# car-dashboard_v1.net
KiCad netlist of a schematic drawn in EAGLE
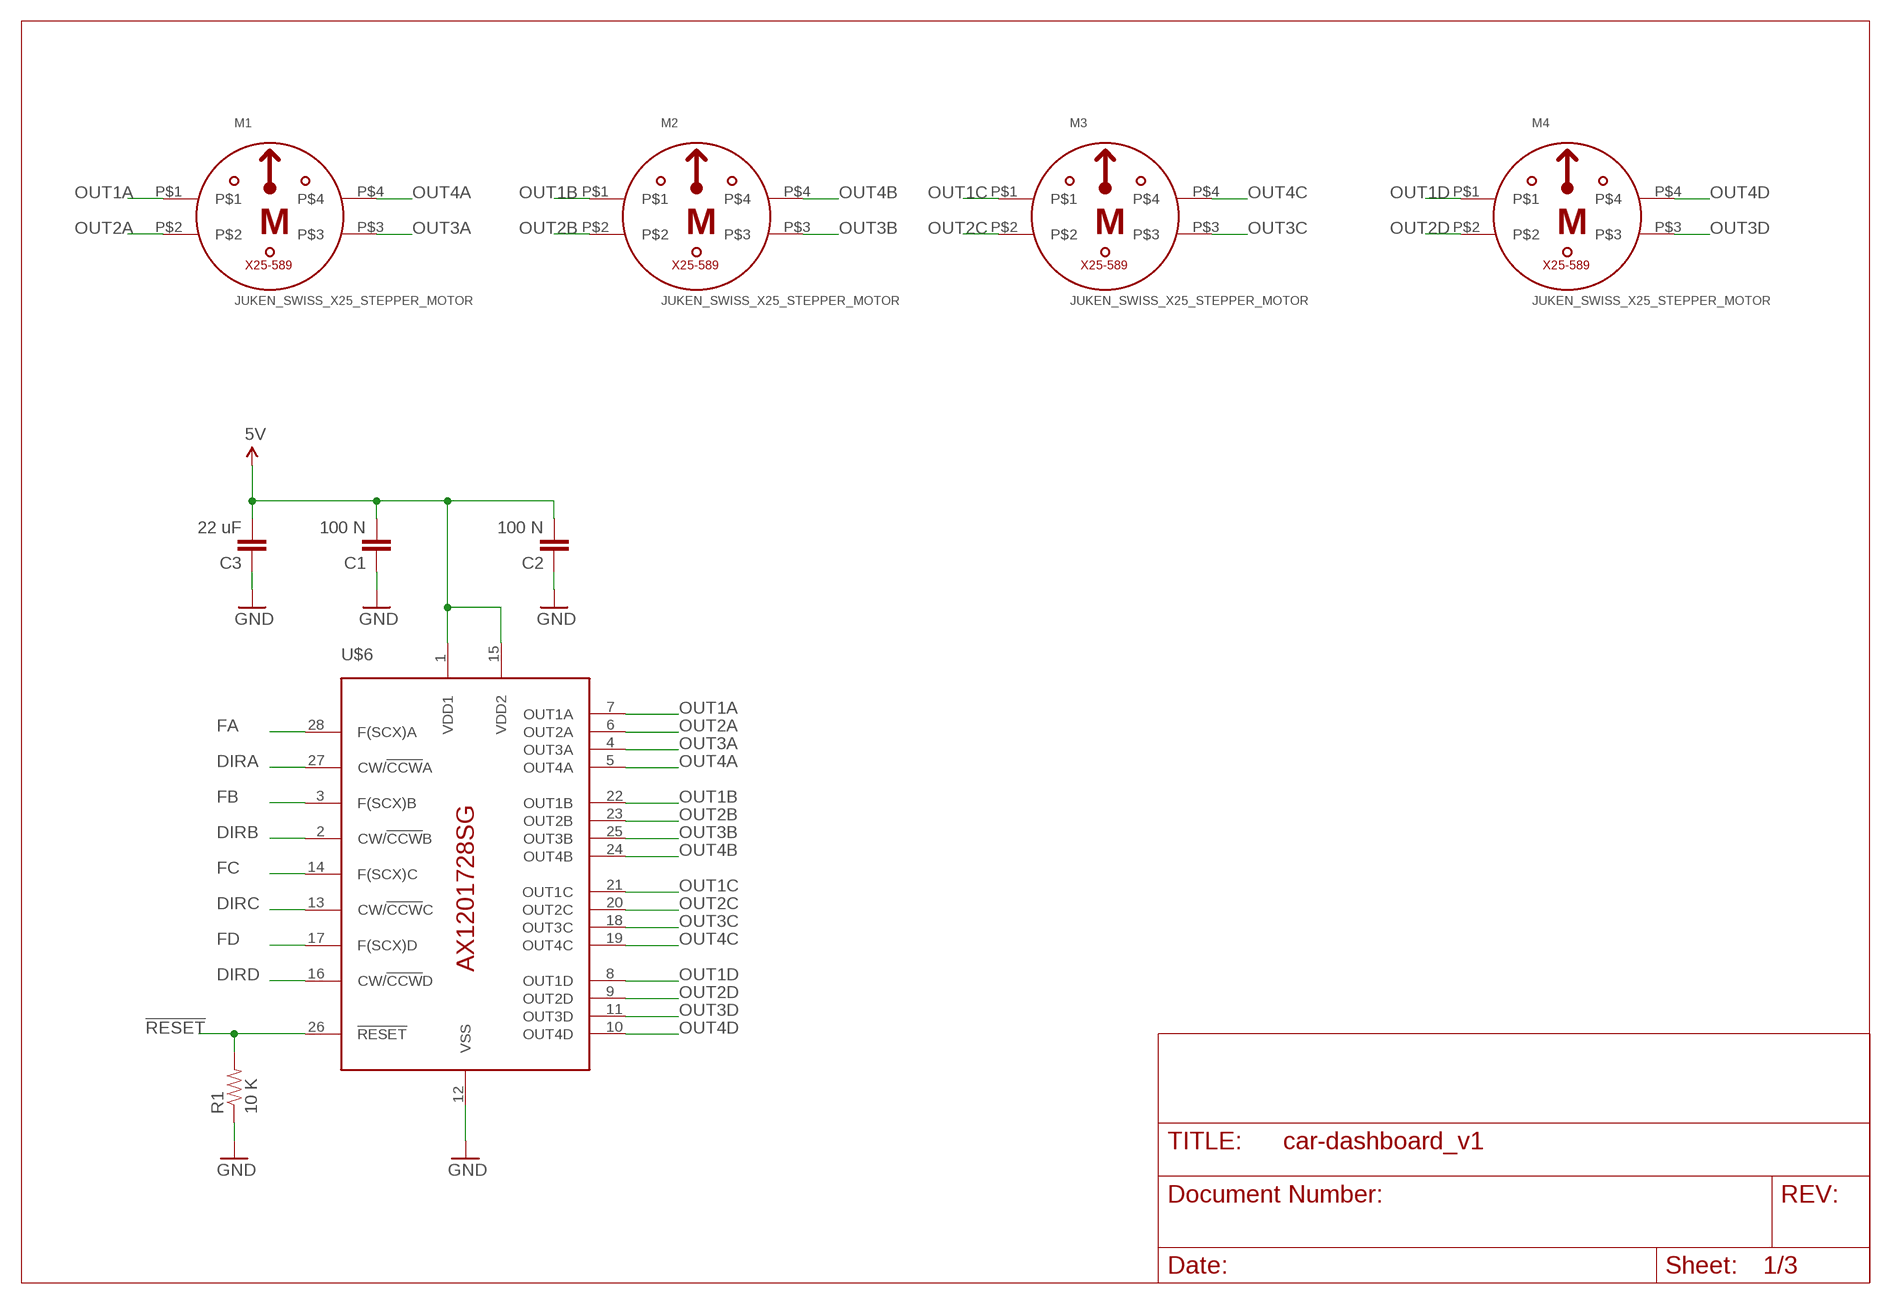
[diagram p0: schematic, sheet 1]
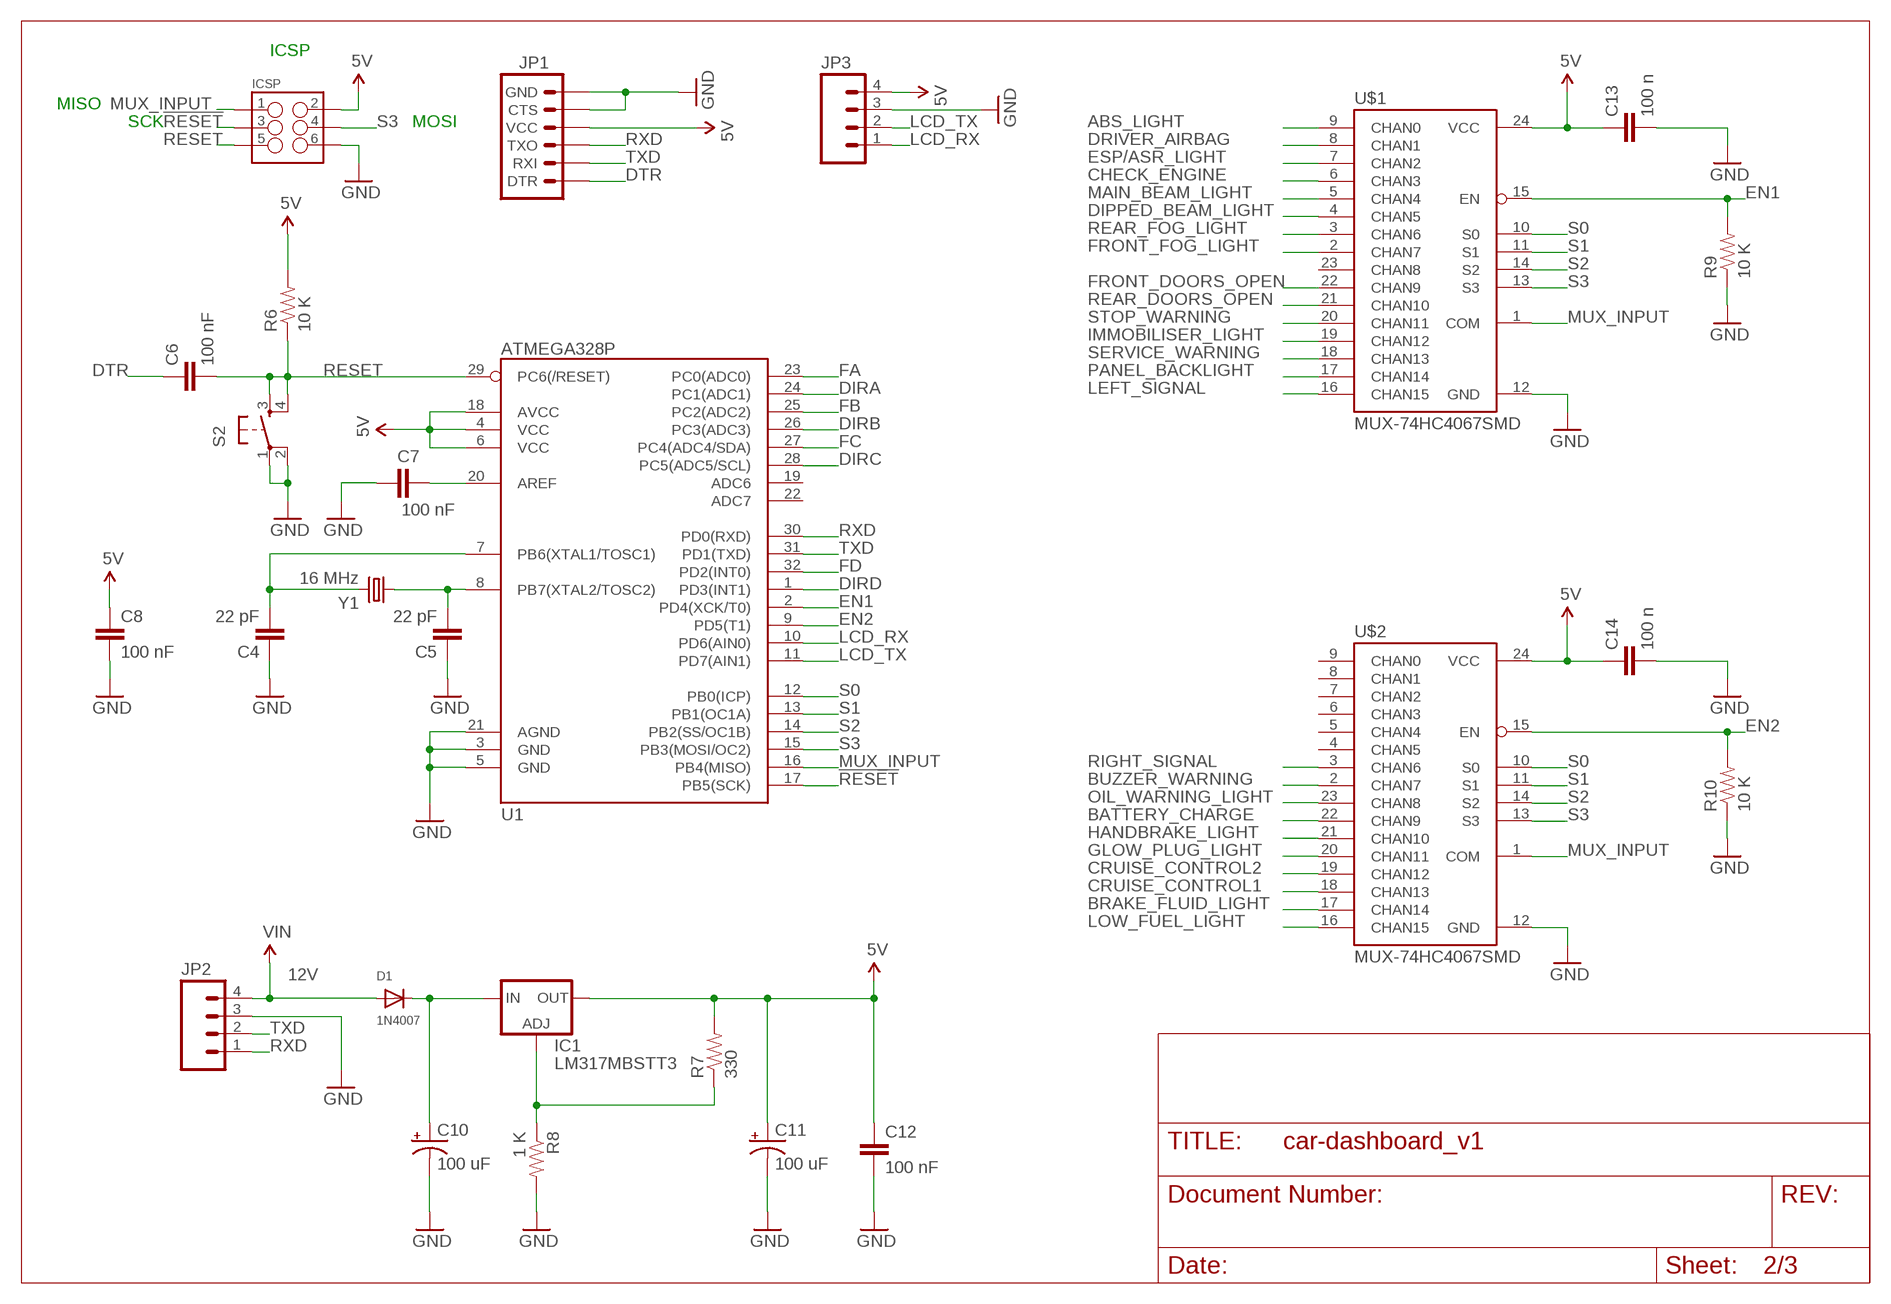
[diagram p1: schematic, sheet 2]
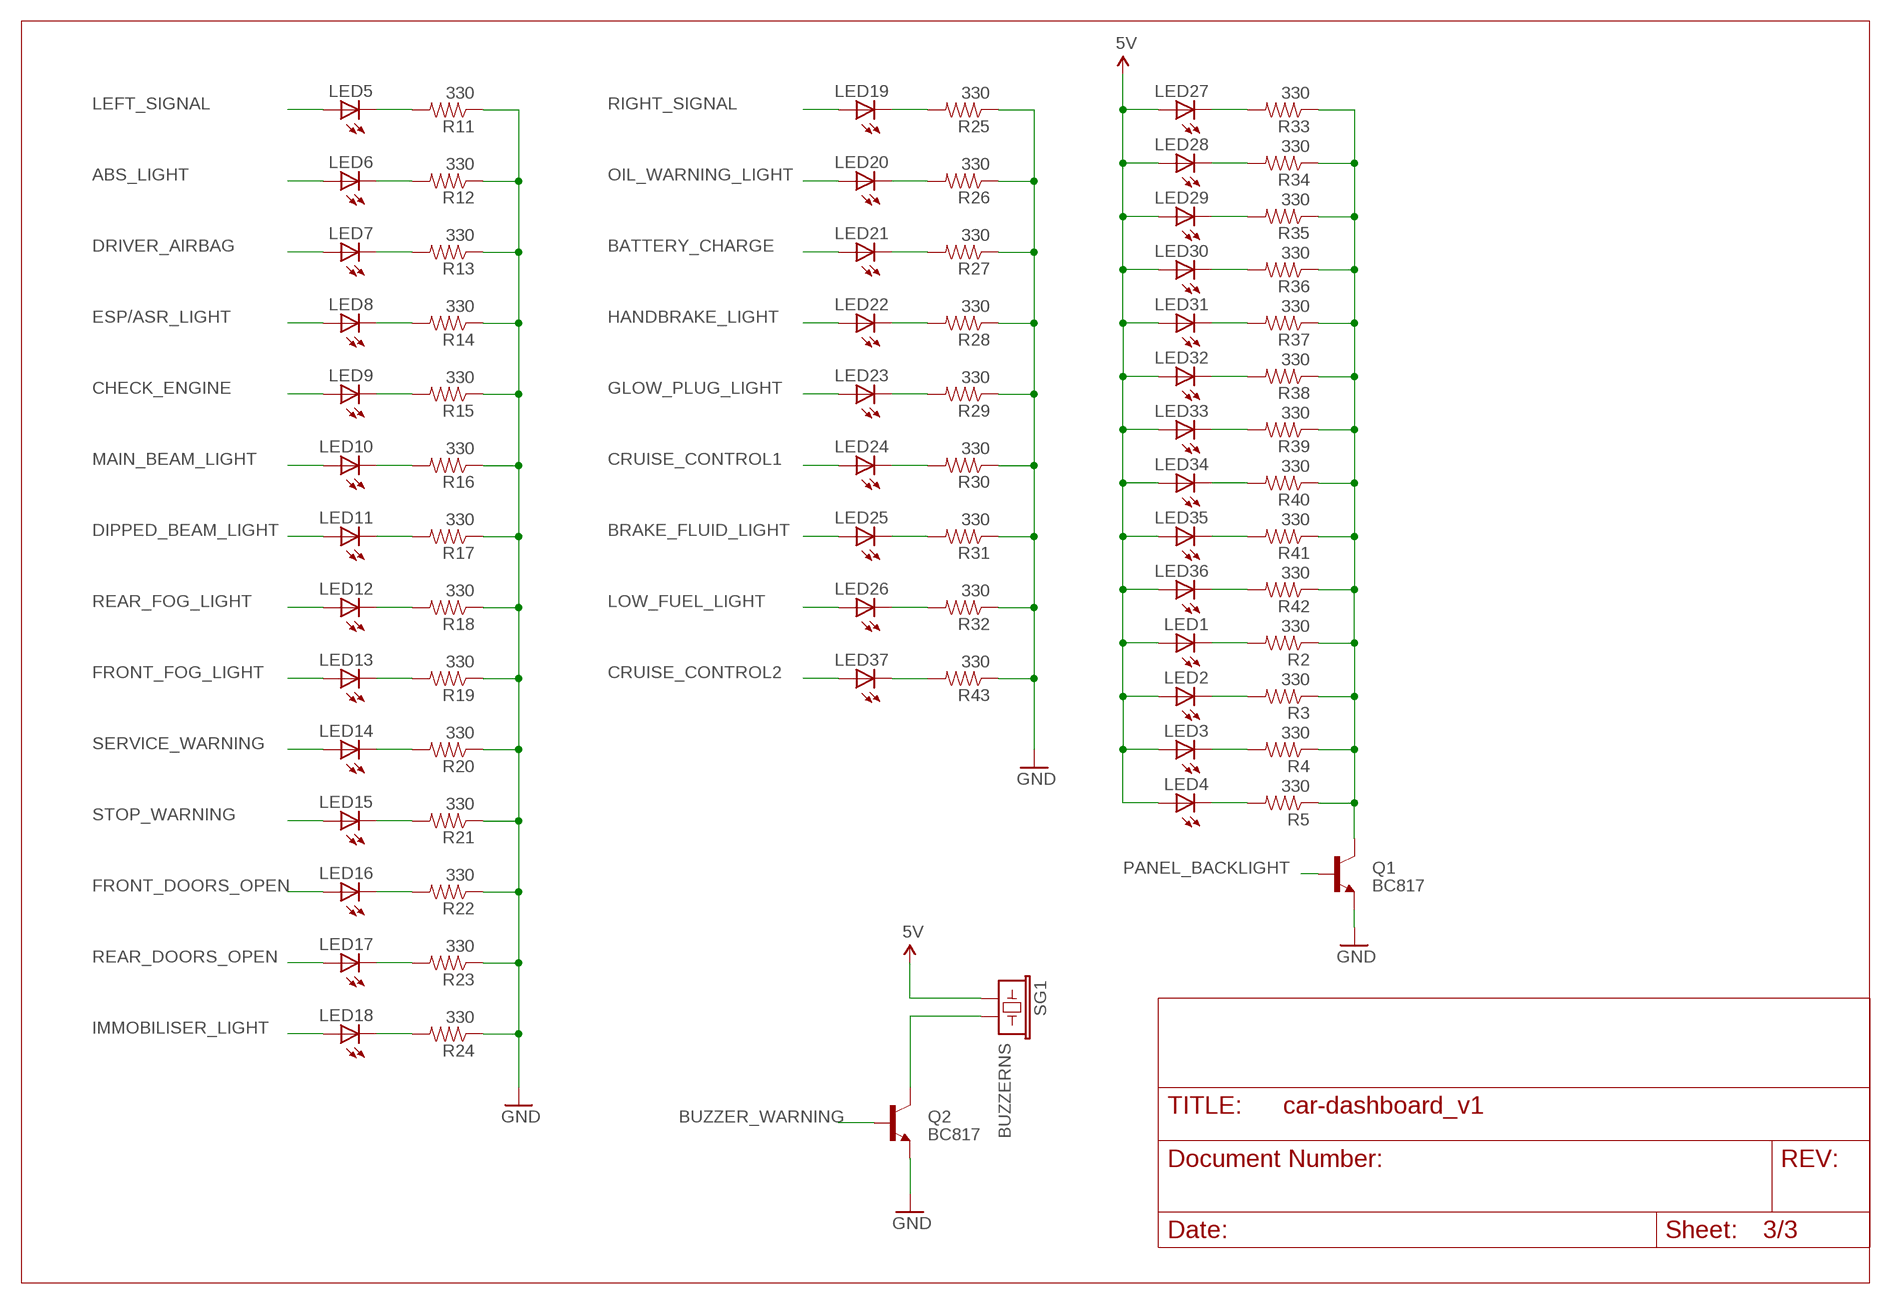
[diagram p2: schematic, sheet 3]

(export (version "E")
  (design (tool "Eeschema 10.0.6"))
  (components
    (comp (ref "C4")
      (value "22 pF")
      (footprint "eagle-import:C0805")
      (libsource (lib "eagle-import") (part "CAPC0805"))
    )
    (comp (ref "C5")
      (value "22 pF")
      (footprint "eagle-import:C0805")
      (libsource (lib "eagle-import") (part "CAPC0805"))
    )
    (comp (ref "C6")
      (value "100 nF")
      (footprint "eagle-import:C0805")
      (libsource (lib "eagle-import") (part "CAPC0805"))
    )
    (comp (ref "C7")
      (value "100 nF")
      (footprint "eagle-import:C0805")
      (libsource (lib "eagle-import") (part "CAPC0805"))
    )
    (comp (ref "C8")
      (value "100 nF")
      (footprint "eagle-import:C0805")
      (libsource (lib "eagle-import") (part "CAPC0805"))
    )
    (comp (ref "C10")
      (value "100 uF")
      (footprint "eagle-import:PANASONIC_F")
      (libsource (lib "eagle-import") (part "CPOL-USF"))
    )
    (comp (ref "C11")
      (value "100 uF")
      (footprint "eagle-import:PANASONIC_F")
      (libsource (lib "eagle-import") (part "CPOL-USF"))
    )
    (comp (ref "C12")
      (value "100 nF")
      (footprint "eagle-import:C0805")
      (libsource (lib "eagle-import") (part "CAPC0805"))
    )
    (comp (ref "C13")
      (value "100 n")
      (footprint "eagle-import:C0805")
      (libsource (lib "eagle-import") (part "CAP0805"))
    )
    (comp (ref "C14")
      (value "100 n")
      (footprint "eagle-import:C0805")
      (libsource (lib "eagle-import") (part "CAP0805"))
    )
    (comp (ref "D1")
      (value "1N4007")
      (footprint "eagle-import:SMADIODE")
      (libsource (lib "eagle-import") (part "DIODESMA"))
    )
    (comp (ref "IC1")
      (value "LM317MBSTT3")
      (footprint "eagle-import:SOT223")
      (libsource (lib "eagle-import") (part "LM317?MBSTT3"))
    )
    (comp (ref "ICSP")
      (value "M03X22X3_SILK_SM")
      (footprint "eagle-import:2X3")
      (libsource (lib "eagle-import") (part "M03X22X3_SILK_SM"))
    )
    (comp (ref "JP1")
      (value "ARDUINO_SERIAL_PROGRAMPTH")
      (footprint "eagle-import:1X06")
      (libsource (lib "eagle-import") (part "ARDUINO_SERIAL_PROGRAMPTH"))
    )
    (comp (ref "JP2")
      (value "M04POLAR")
      (footprint "eagle-import:MOLEX-1X4")
      (libsource (lib "eagle-import") (part "M04POLAR"))
    )
    (comp (ref "JP3")
      (value "M04POLAR")
      (footprint "eagle-import:MOLEX-1X4")
      (libsource (lib "eagle-import") (part "M04POLAR"))
    )
    (comp (ref "R6")
      (value "10 K")
      (footprint "eagle-import:R0805")
      (libsource (lib "eagle-import") (part "RESISTOR0805-RES"))
    )
    (comp (ref "R7")
      (value "330")
      (footprint "eagle-import:R0805")
      (libsource (lib "eagle-import") (part "RESISTOR0805-RES"))
    )
    (comp (ref "R8")
      (value "1 K")
      (footprint "eagle-import:R0805")
      (libsource (lib "eagle-import") (part "RESISTOR0805-RES"))
    )
    (comp (ref "R9")
      (value "10 K")
      (footprint "eagle-import:R0805")
      (libsource (lib "eagle-import") (part "RESISTOR0805-RES"))
    )
    (comp (ref "R10")
      (value "10 K")
      (footprint "eagle-import:R0805")
      (libsource (lib "eagle-import") (part "RESISTOR0805-RES"))
    )
    (comp (ref "S2")
      (value "TAC_SWITCHPTH")
      (footprint "eagle-import:TACTILE-PTH")
      (libsource (lib "eagle-import") (part "TAC_SWITCHPTH"))
    )
    (comp (ref "U$1")
      (value "MUX-74HC4067SMD")
      (footprint "eagle-import:SSOP24")
      (libsource (lib "eagle-import") (part "MUX-74HC4067SMD"))
    )
    (comp (ref "U$2")
      (value "MUX-74HC4067SMD")
      (footprint "eagle-import:SSOP24")
      (libsource (lib "eagle-import") (part "MUX-74HC4067SMD"))
    )
    (comp (ref "U1")
      (value "ATMEGA328P")
      (footprint "eagle-import:TQFP32-08")
      (libsource (lib "eagle-import") (part "ATMEGA328_SMT"))
    )
    (comp (ref "Y1")
      (value "16 MHz")
      (footprint "eagle-import:HC49UP")
      (libsource (lib "eagle-import") (part "CRYSTALSMD"))
    )
    (comp (ref "LED1")
      (value "LEDCHIPLED_0805")
      (footprint "eagle-import:CHIPLED_0805")
      (libsource (lib "eagle-import") (part "LEDCHIPLED_0805"))
    )
    (comp (ref "LED2")
      (value "LEDCHIPLED_0805")
      (footprint "eagle-import:CHIPLED_0805")
      (libsource (lib "eagle-import") (part "LEDCHIPLED_0805"))
    )
    (comp (ref "LED3")
      (value "LEDCHIPLED_0805")
      (footprint "eagle-import:CHIPLED_0805")
      (libsource (lib "eagle-import") (part "LEDCHIPLED_0805"))
    )
    (comp (ref "LED4")
      (value "LEDCHIPLED_0805")
      (footprint "eagle-import:CHIPLED_0805")
      (libsource (lib "eagle-import") (part "LEDCHIPLED_0805"))
    )
    (comp (ref "LED5")
      (value "LEDCHIPLED_0805")
      (footprint "eagle-import:CHIPLED_0805")
      (libsource (lib "eagle-import") (part "LEDCHIPLED_0805"))
    )
    (comp (ref "LED6")
      (value "LEDCHIPLED_0805")
      (footprint "eagle-import:CHIPLED_0805")
      (libsource (lib "eagle-import") (part "LEDCHIPLED_0805"))
    )
    (comp (ref "LED7")
      (value "LEDCHIPLED_0805")
      (footprint "eagle-import:CHIPLED_0805")
      (libsource (lib "eagle-import") (part "LEDCHIPLED_0805"))
    )
    (comp (ref "LED8")
      (value "LEDCHIPLED_0805")
      (footprint "eagle-import:CHIPLED_0805")
      (libsource (lib "eagle-import") (part "LEDCHIPLED_0805"))
    )
    (comp (ref "LED9")
      (value "LEDCHIPLED_0805")
      (footprint "eagle-import:CHIPLED_0805")
      (libsource (lib "eagle-import") (part "LEDCHIPLED_0805"))
    )
    (comp (ref "LED10")
      (value "LEDCHIPLED_0805")
      (footprint "eagle-import:CHIPLED_0805")
      (libsource (lib "eagle-import") (part "LEDCHIPLED_0805"))
    )
    (comp (ref "LED11")
      (value "LEDCHIPLED_0805")
      (footprint "eagle-import:CHIPLED_0805")
      (libsource (lib "eagle-import") (part "LEDCHIPLED_0805"))
    )
    (comp (ref "LED12")
      (value "LEDCHIPLED_0805")
      (footprint "eagle-import:CHIPLED_0805")
      (libsource (lib "eagle-import") (part "LEDCHIPLED_0805"))
    )
    (comp (ref "LED13")
      (value "LEDCHIPLED_0805")
      (footprint "eagle-import:CHIPLED_0805")
      (libsource (lib "eagle-import") (part "LEDCHIPLED_0805"))
    )
    (comp (ref "LED14")
      (value "LEDCHIPLED_0805")
      (footprint "eagle-import:CHIPLED_0805")
      (libsource (lib "eagle-import") (part "LEDCHIPLED_0805"))
    )
    (comp (ref "LED15")
      (value "LEDCHIPLED_0805")
      (footprint "eagle-import:CHIPLED_0805")
      (libsource (lib "eagle-import") (part "LEDCHIPLED_0805"))
    )
    (comp (ref "LED16")
      (value "LEDCHIPLED_0805")
      (footprint "eagle-import:CHIPLED_0805")
      (libsource (lib "eagle-import") (part "LEDCHIPLED_0805"))
    )
    (comp (ref "LED17")
      (value "LEDCHIPLED_0805")
      (footprint "eagle-import:CHIPLED_0805")
      (libsource (lib "eagle-import") (part "LEDCHIPLED_0805"))
    )
    (comp (ref "LED18")
      (value "LEDCHIPLED_0805")
      (footprint "eagle-import:CHIPLED_0805")
      (libsource (lib "eagle-import") (part "LEDCHIPLED_0805"))
    )
    (comp (ref "LED19")
      (value "LEDCHIPLED_0805")
      (footprint "eagle-import:CHIPLED_0805")
      (libsource (lib "eagle-import") (part "LEDCHIPLED_0805"))
    )
    (comp (ref "LED20")
      (value "LEDCHIPLED_0805")
      (footprint "eagle-import:CHIPLED_0805")
      (libsource (lib "eagle-import") (part "LEDCHIPLED_0805"))
    )
    (comp (ref "LED21")
      (value "LEDCHIPLED_0805")
      (footprint "eagle-import:CHIPLED_0805")
      (libsource (lib "eagle-import") (part "LEDCHIPLED_0805"))
    )
    (comp (ref "LED22")
      (value "LEDCHIPLED_0805")
      (footprint "eagle-import:CHIPLED_0805")
      (libsource (lib "eagle-import") (part "LEDCHIPLED_0805"))
    )
    (comp (ref "LED23")
      (value "LEDCHIPLED_0805")
      (footprint "eagle-import:CHIPLED_0805")
      (libsource (lib "eagle-import") (part "LEDCHIPLED_0805"))
    )
    (comp (ref "LED24")
      (value "LEDCHIPLED_0805")
      (footprint "eagle-import:CHIPLED_0805")
      (libsource (lib "eagle-import") (part "LEDCHIPLED_0805"))
    )
    (comp (ref "LED25")
      (value "LEDCHIPLED_0805")
      (footprint "eagle-import:CHIPLED_0805")
      (libsource (lib "eagle-import") (part "LEDCHIPLED_0805"))
    )
    (comp (ref "LED26")
      (value "LEDCHIPLED_0805")
      (footprint "eagle-import:CHIPLED_0805")
      (libsource (lib "eagle-import") (part "LEDCHIPLED_0805"))
    )
    (comp (ref "LED27")
      (value "LEDCHIPLED_0805")
      (footprint "eagle-import:CHIPLED_0805")
      (libsource (lib "eagle-import") (part "LEDCHIPLED_0805"))
    )
    (comp (ref "LED28")
      (value "LEDCHIPLED_0805")
      (footprint "eagle-import:CHIPLED_0805")
      (libsource (lib "eagle-import") (part "LEDCHIPLED_0805"))
    )
    (comp (ref "LED29")
      (value "LEDCHIPLED_0805")
      (footprint "eagle-import:CHIPLED_0805")
      (libsource (lib "eagle-import") (part "LEDCHIPLED_0805"))
    )
    (comp (ref "LED30")
      (value "LEDCHIPLED_0805")
      (footprint "eagle-import:CHIPLED_0805")
      (libsource (lib "eagle-import") (part "LEDCHIPLED_0805"))
    )
    (comp (ref "LED31")
      (value "LEDCHIPLED_0805")
      (footprint "eagle-import:CHIPLED_0805")
      (libsource (lib "eagle-import") (part "LEDCHIPLED_0805"))
    )
    (comp (ref "LED32")
      (value "LEDCHIPLED_0805")
      (footprint "eagle-import:CHIPLED_0805")
      (libsource (lib "eagle-import") (part "LEDCHIPLED_0805"))
    )
    (comp (ref "LED33")
      (value "LEDCHIPLED_0805")
      (footprint "eagle-import:CHIPLED_0805")
      (libsource (lib "eagle-import") (part "LEDCHIPLED_0805"))
    )
    (comp (ref "LED34")
      (value "LEDCHIPLED_0805")
      (footprint "eagle-import:CHIPLED_0805")
      (libsource (lib "eagle-import") (part "LEDCHIPLED_0805"))
    )
    (comp (ref "LED35")
      (value "LEDCHIPLED_0805")
      (footprint "eagle-import:CHIPLED_0805")
      (libsource (lib "eagle-import") (part "LEDCHIPLED_0805"))
    )
    (comp (ref "LED36")
      (value "LEDCHIPLED_0805")
      (footprint "eagle-import:CHIPLED_0805")
      (libsource (lib "eagle-import") (part "LEDCHIPLED_0805"))
    )
    (comp (ref "LED37")
      (value "LEDCHIPLED_0805")
      (footprint "eagle-import:CHIPLED_0805")
      (libsource (lib "eagle-import") (part "LEDCHIPLED_0805"))
    )
    (comp (ref "Q1")
      (value "BC817")
      (footprint "eagle-import:SOT23-3")
      (libsource (lib "eagle-import") (part "TRANSISTOR_NPNSOT23-3"))
    )
    (comp (ref "Q2")
      (value "BC817")
      (footprint "eagle-import:SOT23-3")
      (libsource (lib "eagle-import") (part "TRANSISTOR_NPNSOT23-3"))
    )
    (comp (ref "R2")
      (value "330")
      (footprint "eagle-import:0805")
      (libsource (lib "eagle-import") (part "SparkFun-Resistors_RESISTOR0805-RES"))
    )
    (comp (ref "R3")
      (value "330")
      (footprint "eagle-import:0805")
      (libsource (lib "eagle-import") (part "SparkFun-Resistors_RESISTOR0805-RES"))
    )
    (comp (ref "R4")
      (value "330")
      (footprint "eagle-import:0805")
      (libsource (lib "eagle-import") (part "SparkFun-Resistors_RESISTOR0805-RES"))
    )
    (comp (ref "R5")
      (value "330")
      (footprint "eagle-import:0805")
      (libsource (lib "eagle-import") (part "SparkFun-Resistors_RESISTOR0805-RES"))
    )
    (comp (ref "R11")
      (value "330")
      (footprint "eagle-import:0805")
      (libsource (lib "eagle-import") (part "SparkFun-Resistors_RESISTOR0805-RES"))
    )
    (comp (ref "R12")
      (value "330")
      (footprint "eagle-import:0805")
      (libsource (lib "eagle-import") (part "SparkFun-Resistors_RESISTOR0805-RES"))
    )
    (comp (ref "R13")
      (value "330")
      (footprint "eagle-import:0805")
      (libsource (lib "eagle-import") (part "SparkFun-Resistors_RESISTOR0805-RES"))
    )
    (comp (ref "R14")
      (value "330")
      (footprint "eagle-import:0805")
      (libsource (lib "eagle-import") (part "SparkFun-Resistors_RESISTOR0805-RES"))
    )
    (comp (ref "R15")
      (value "330")
      (footprint "eagle-import:0805")
      (libsource (lib "eagle-import") (part "SparkFun-Resistors_RESISTOR0805-RES"))
    )
    (comp (ref "R16")
      (value "330")
      (footprint "eagle-import:0805")
      (libsource (lib "eagle-import") (part "SparkFun-Resistors_RESISTOR0805-RES"))
    )
    (comp (ref "R17")
      (value "330")
      (footprint "eagle-import:0805")
      (libsource (lib "eagle-import") (part "SparkFun-Resistors_RESISTOR0805-RES"))
    )
    (comp (ref "R18")
      (value "330")
      (footprint "eagle-import:0805")
      (libsource (lib "eagle-import") (part "SparkFun-Resistors_RESISTOR0805-RES"))
    )
    (comp (ref "R19")
      (value "330")
      (footprint "eagle-import:0805")
      (libsource (lib "eagle-import") (part "SparkFun-Resistors_RESISTOR0805-RES"))
    )
    (comp (ref "R20")
      (value "330")
      (footprint "eagle-import:0805")
      (libsource (lib "eagle-import") (part "SparkFun-Resistors_RESISTOR0805-RES"))
    )
    (comp (ref "R21")
      (value "330")
      (footprint "eagle-import:0805")
      (libsource (lib "eagle-import") (part "SparkFun-Resistors_RESISTOR0805-RES"))
    )
    (comp (ref "R22")
      (value "330")
      (footprint "eagle-import:0805")
      (libsource (lib "eagle-import") (part "SparkFun-Resistors_RESISTOR0805-RES"))
    )
    (comp (ref "R23")
      (value "330")
      (footprint "eagle-import:0805")
      (libsource (lib "eagle-import") (part "SparkFun-Resistors_RESISTOR0805-RES"))
    )
    (comp (ref "R24")
      (value "330")
      (footprint "eagle-import:0805")
      (libsource (lib "eagle-import") (part "SparkFun-Resistors_RESISTOR0805-RES"))
    )
    (comp (ref "R25")
      (value "330")
      (footprint "eagle-import:0805")
      (libsource (lib "eagle-import") (part "SparkFun-Resistors_RESISTOR0805-RES"))
    )
    (comp (ref "R26")
      (value "330")
      (footprint "eagle-import:0805")
      (libsource (lib "eagle-import") (part "SparkFun-Resistors_RESISTOR0805-RES"))
    )
    (comp (ref "R27")
      (value "330")
      (footprint "eagle-import:0805")
      (libsource (lib "eagle-import") (part "SparkFun-Resistors_RESISTOR0805-RES"))
    )
    (comp (ref "R28")
      (value "330")
      (footprint "eagle-import:0805")
      (libsource (lib "eagle-import") (part "SparkFun-Resistors_RESISTOR0805-RES"))
    )
    (comp (ref "R29")
      (value "330")
      (footprint "eagle-import:0805")
      (libsource (lib "eagle-import") (part "SparkFun-Resistors_RESISTOR0805-RES"))
    )
    (comp (ref "R30")
      (value "330")
      (footprint "eagle-import:0805")
      (libsource (lib "eagle-import") (part "SparkFun-Resistors_RESISTOR0805-RES"))
    )
    (comp (ref "R31")
      (value "330")
      (footprint "eagle-import:0805")
      (libsource (lib "eagle-import") (part "SparkFun-Resistors_RESISTOR0805-RES"))
    )
    (comp (ref "R32")
      (value "330")
      (footprint "eagle-import:0805")
      (libsource (lib "eagle-import") (part "SparkFun-Resistors_RESISTOR0805-RES"))
    )
    (comp (ref "R33")
      (value "330")
      (footprint "eagle-import:0805")
      (libsource (lib "eagle-import") (part "SparkFun-Resistors_RESISTOR0805-RES"))
    )
    (comp (ref "R34")
      (value "330")
      (footprint "eagle-import:0805")
      (libsource (lib "eagle-import") (part "SparkFun-Resistors_RESISTOR0805-RES"))
    )
    (comp (ref "R35")
      (value "330")
      (footprint "eagle-import:0805")
      (libsource (lib "eagle-import") (part "SparkFun-Resistors_RESISTOR0805-RES"))
    )
    (comp (ref "R36")
      (value "330")
      (footprint "eagle-import:0805")
      (libsource (lib "eagle-import") (part "SparkFun-Resistors_RESISTOR0805-RES"))
    )
    (comp (ref "R37")
      (value "330")
      (footprint "eagle-import:0805")
      (libsource (lib "eagle-import") (part "SparkFun-Resistors_RESISTOR0805-RES"))
    )
    (comp (ref "R38")
      (value "330")
      (footprint "eagle-import:0805")
      (libsource (lib "eagle-import") (part "SparkFun-Resistors_RESISTOR0805-RES"))
    )
    (comp (ref "R39")
      (value "330")
      (footprint "eagle-import:0805")
      (libsource (lib "eagle-import") (part "SparkFun-Resistors_RESISTOR0805-RES"))
    )
    (comp (ref "R40")
      (value "330")
      (footprint "eagle-import:0805")
      (libsource (lib "eagle-import") (part "SparkFun-Resistors_RESISTOR0805-RES"))
    )
    (comp (ref "R41")
      (value "330")
      (footprint "eagle-import:0805")
      (libsource (lib "eagle-import") (part "SparkFun-Resistors_RESISTOR0805-RES"))
    )
    (comp (ref "R42")
      (value "330")
      (footprint "eagle-import:0805")
      (libsource (lib "eagle-import") (part "SparkFun-Resistors_RESISTOR0805-RES"))
    )
    (comp (ref "R43")
      (value "330")
      (footprint "eagle-import:0805")
      (libsource (lib "eagle-import") (part "SparkFun-Resistors_RESISTOR0805-RES"))
    )
    (comp (ref "SG1")
      (value "BUZZERNS")
      (footprint "eagle-import:BUZZER-12MM-NS")
      (libsource (lib "eagle-import") (part "BUZZERNS"))
    )
    (comp (ref "C1")
      (value "100 N")
      (footprint "eagle-import:C0805")
      (libsource (lib "eagle-import") (part "CAP0805"))
    )
    (comp (ref "C2")
      (value "100 N")
      (footprint "eagle-import:C0805")
      (libsource (lib "eagle-import") (part "CAP0805"))
    )
    (comp (ref "C3")
      (value "22 uF")
      (footprint "eagle-import:C0805")
      (libsource (lib "eagle-import") (part "CAP0805"))
    )
    (comp (ref "M1")
      (value "JUKEN_SWISS_X25_STEPPER_MOTOR")
      (footprint "eagle-import:X25_STEPPER_MOTOR")
      (libsource (lib "eagle-import") (part "JUKEN_SWISS_X25_STEPPER_MOTOR"))
    )
    (comp (ref "M2")
      (value "JUKEN_SWISS_X25_STEPPER_MOTOR")
      (footprint "eagle-import:X25_STEPPER_MOTOR")
      (libsource (lib "eagle-import") (part "JUKEN_SWISS_X25_STEPPER_MOTOR"))
    )
    (comp (ref "M3")
      (value "JUKEN_SWISS_X25_STEPPER_MOTOR")
      (footprint "eagle-import:X25_STEPPER_MOTOR")
      (libsource (lib "eagle-import") (part "JUKEN_SWISS_X25_STEPPER_MOTOR"))
    )
    (comp (ref "M4")
      (value "JUKEN_SWISS_X25_STEPPER_MOTOR")
      (footprint "eagle-import:X25_STEPPER_MOTOR")
      (libsource (lib "eagle-import") (part "JUKEN_SWISS_X25_STEPPER_MOTOR"))
    )
    (comp (ref "R1")
      (value "10 K")
      (footprint "eagle-import:0805")
      (libsource (lib "eagle-import") (part "SparkFun-Resistors_RESISTOR0805-RES"))
    )
    (comp (ref "U$6")
      (value "AX1201728SG-X25_DRIVER")
      (footprint "eagle-import:SOL-28")
      (libsource (lib "eagle-import") (part "AX1201728SG-X25_DRIVER"))
    )
  )
  (nets
    (net (code "1") (name "5V") (class "Default")
      (node (ref "C1") (pin "2") (pinfunction "2_2") (pintype "passive"))
      (node (ref "C11") (pin "+") (pinfunction "+_+") (pintype "passive"))
      (node (ref "C12") (pin "1") (pinfunction "1_1") (pintype "passive"))
      (node (ref "C13") (pin "1") (pinfunction "1_1") (pintype "passive"))
      (node (ref "C14") (pin "1") (pinfunction "1_1") (pintype "passive"))
      (node (ref "C2") (pin "2") (pinfunction "2_2") (pintype "passive"))
      (node (ref "C3") (pin "2") (pinfunction "2_2") (pintype "passive"))
      (node (ref "C8") (pin "1") (pinfunction "1_1") (pintype "passive"))
      (node (ref "IC1") (pin "4") (pinfunction "OUT_4") (pintype "passive"))
      (node (ref "ICSP") (pin "2") (pinfunction "2_2") (pintype "bidirectional"))
      (node (ref "JP1") (pin "4") (pinfunction "VCC_4") (pintype "passive"))
      (node (ref "JP3") (pin "4") (pinfunction "4_4") (pintype "passive"))
      (node (ref "LED1") (pin "A") (pinfunction "A_A") (pintype "passive"))
      (node (ref "LED2") (pin "A") (pinfunction "A_A") (pintype "passive"))
      (node (ref "LED27") (pin "A") (pinfunction "A_A") (pintype "passive"))
      (node (ref "LED28") (pin "A") (pinfunction "A_A") (pintype "passive"))
      (node (ref "LED29") (pin "A") (pinfunction "A_A") (pintype "passive"))
      (node (ref "LED3") (pin "A") (pinfunction "A_A") (pintype "passive"))
      (node (ref "LED30") (pin "A") (pinfunction "A_A") (pintype "passive"))
      (node (ref "LED31") (pin "A") (pinfunction "A_A") (pintype "passive"))
      (node (ref "LED32") (pin "A") (pinfunction "A_A") (pintype "passive"))
      (node (ref "LED33") (pin "A") (pinfunction "A_A") (pintype "passive"))
      (node (ref "LED34") (pin "A") (pinfunction "A_A") (pintype "passive"))
      (node (ref "LED35") (pin "A") (pinfunction "A_A") (pintype "passive"))
      (node (ref "LED36") (pin "A") (pinfunction "A_A") (pintype "passive"))
      (node (ref "LED4") (pin "A") (pinfunction "A_A") (pintype "passive"))
      (node (ref "R6") (pin "2") (pinfunction "2_2") (pintype "passive"))
      (node (ref "R7") (pin "2") (pinfunction "2_2") (pintype "passive"))
      (node (ref "SG1") (pin "+") (pinfunction "1_+") (pintype "passive"))
      (node (ref "U$1") (pin "24") (pinfunction "VCC_24") (pintype "bidirectional"))
      (node (ref "U$2") (pin "24") (pinfunction "VCC_24") (pintype "bidirectional"))
      (node (ref "U$6") (pin "1") (pinfunction "VDD1_1") (pintype "bidirectional"))
      (node (ref "U$6") (pin "15") (pinfunction "VDD2_15") (pintype "bidirectional"))
      (node (ref "U1") (pin "18") (pinfunction "AVCC_18") (pintype "bidirectional"))
      (node (ref "U1") (pin "4") (pinfunction "VCC_4") (pintype "bidirectional"))
      (node (ref "U1") (pin "6") (pinfunction "VCC_6") (pintype "bidirectional"))
    )
    (net (code "2") (name "12V") (class "Default")
      (node (ref "D1") (pin "A") (pinfunction "A_A") (pintype "passive"))
      (node (ref "JP2") (pin "4") (pinfunction "4_4") (pintype "passive"))
    )
    (net (code "3") (name "ABS_LIGHT") (class "Default")
      (node (ref "LED6") (pin "A") (pinfunction "A_A") (pintype "passive"))
      (node (ref "U$1") (pin "9") (pinfunction "CHAN0_9") (pintype "bidirectional"))
    )
    (net (code "4") (name "BATTERY_CHARGE") (class "Default")
      (node (ref "LED21") (pin "A") (pinfunction "A_A") (pintype "passive"))
      (node (ref "U$2") (pin "22") (pinfunction "CHAN9_22") (pintype "bidirectional"))
    )
    (net (code "5") (name "BRAKE_FLUID_LIGHT") (class "Default")
      (node (ref "LED25") (pin "A") (pinfunction "A_A") (pintype "passive"))
      (node (ref "U$2") (pin "17") (pinfunction "CHAN14_17") (pintype "bidirectional"))
    )
    (net (code "6") (name "BUZZER_WARNING") (class "Default")
      (node (ref "Q2") (pin "1") (pinfunction "B_1") (pintype "passive"))
      (node (ref "U$2") (pin "2") (pinfunction "CHAN7_2") (pintype "bidirectional"))
    )
    (net (code "7") (name "CHECK_ENGINE") (class "Default")
      (node (ref "LED9") (pin "A") (pinfunction "A_A") (pintype "passive"))
      (node (ref "U$1") (pin "6") (pinfunction "CHAN3_6") (pintype "bidirectional"))
    )
    (net (code "8") (name "CRUISE_CONTROL1") (class "Default")
      (node (ref "LED24") (pin "A") (pinfunction "A_A") (pintype "passive"))
      (node (ref "U$2") (pin "18") (pinfunction "CHAN13_18") (pintype "bidirectional"))
    )
    (net (code "9") (name "CRUISE_CONTROL2") (class "Default")
      (node (ref "LED37") (pin "A") (pinfunction "A_A") (pintype "passive"))
      (node (ref "U$2") (pin "19") (pinfunction "CHAN12_19") (pintype "bidirectional"))
    )
    (net (code "10") (name "DIPPED_BEAM_LIGHT") (class "Default")
      (node (ref "LED11") (pin "A") (pinfunction "A_A") (pintype "passive"))
      (node (ref "U$1") (pin "4") (pinfunction "CHAN5_4") (pintype "bidirectional"))
    )
    (net (code "11") (name "DIRA") (class "Default")
      (node (ref "U$6") (pin "27") (pinfunction "CW/~{CCW}A_27") (pintype "bidirectional"))
      (node (ref "U1") (pin "24") (pinfunction "PC1(ADC1)_24") (pintype "bidirectional"))
    )
    (net (code "12") (name "DIRB") (class "Default")
      (node (ref "U$6") (pin "2") (pinfunction "CW/~{CCW}B_2") (pintype "bidirectional"))
      (node (ref "U1") (pin "26") (pinfunction "PC3(ADC3)_26") (pintype "bidirectional"))
    )
    (net (code "13") (name "DIRC") (class "Default")
      (node (ref "U$6") (pin "13") (pinfunction "CW/~{CCW}C_13") (pintype "bidirectional"))
      (node (ref "U1") (pin "28") (pinfunction "PC5(ADC5/SCL)_28") (pintype "bidirectional"))
    )
    (net (code "14") (name "DIRD") (class "Default")
      (node (ref "U$6") (pin "16") (pinfunction "CW/~{CCW}D_16") (pintype "bidirectional"))
      (node (ref "U1") (pin "1") (pinfunction "PD3(INT1)_1") (pintype "bidirectional"))
    )
    (net (code "15") (name "DRIVER_AIRBAG") (class "Default")
      (node (ref "LED7") (pin "A") (pinfunction "A_A") (pintype "passive"))
      (node (ref "U$1") (pin "8") (pinfunction "CHAN1_8") (pintype "bidirectional"))
    )
    (net (code "16") (name "DTR") (class "Default")
      (node (ref "C6") (pin "1") (pinfunction "1_1") (pintype "passive"))
      (node (ref "JP1") (pin "1") (pinfunction "DTR_1") (pintype "passive"))
    )
    (net (code "17") (name "EN1") (class "Default")
      (node (ref "R9") (pin "2") (pinfunction "2_2") (pintype "passive"))
      (node (ref "U$1") (pin "15") (pinfunction "EN_15") (pintype "input"))
      (node (ref "U1") (pin "2") (pinfunction "PD4(XCK/T0)_2") (pintype "bidirectional"))
    )
    (net (code "18") (name "EN2") (class "Default")
      (node (ref "R10") (pin "2") (pinfunction "2_2") (pintype "passive"))
      (node (ref "U$2") (pin "15") (pinfunction "EN_15") (pintype "input"))
      (node (ref "U1") (pin "9") (pinfunction "PD5(T1)_9") (pintype "bidirectional"))
    )
    (net (code "19") (name "ESP{slash}ASR_LIGHT") (class "Default")
      (node (ref "LED8") (pin "A") (pinfunction "A_A") (pintype "passive"))
      (node (ref "U$1") (pin "7") (pinfunction "CHAN2_7") (pintype "bidirectional"))
    )
    (net (code "20") (name "FA") (class "Default")
      (node (ref "U$6") (pin "28") (pinfunction "F(SCX)A_28") (pintype "bidirectional"))
      (node (ref "U1") (pin "23") (pinfunction "PC0(ADC0)_23") (pintype "bidirectional"))
    )
    (net (code "21") (name "FB") (class "Default")
      (node (ref "U$6") (pin "3") (pinfunction "F(SCX)B_3") (pintype "bidirectional"))
      (node (ref "U1") (pin "25") (pinfunction "PC2(ADC2)_25") (pintype "bidirectional"))
    )
    (net (code "22") (name "FC") (class "Default")
      (node (ref "U$6") (pin "14") (pinfunction "F(SCX)C_14") (pintype "bidirectional"))
      (node (ref "U1") (pin "27") (pinfunction "PC4(ADC4/SDA)_27") (pintype "bidirectional"))
    )
    (net (code "23") (name "FD") (class "Default")
      (node (ref "U$6") (pin "17") (pinfunction "F(SCX)D_17") (pintype "bidirectional"))
      (node (ref "U1") (pin "32") (pinfunction "PD2(INT0)_32") (pintype "bidirectional"))
    )
    (net (code "24") (name "FRONT_DOORS_OPEN") (class "Default")
      (node (ref "LED16") (pin "A") (pinfunction "A_A") (pintype "passive"))
      (node (ref "U$1") (pin "22") (pinfunction "CHAN9_22") (pintype "bidirectional"))
    )
    (net (code "25") (name "FRONT_FOG_LIGHT") (class "Default")
      (node (ref "LED13") (pin "A") (pinfunction "A_A") (pintype "passive"))
      (node (ref "U$1") (pin "2") (pinfunction "CHAN7_2") (pintype "bidirectional"))
    )
    (net (code "26") (name "GLOW_PLUG_LIGHT") (class "Default")
      (node (ref "LED23") (pin "A") (pinfunction "A_A") (pintype "passive"))
      (node (ref "U$2") (pin "20") (pinfunction "CHAN11_20") (pintype "bidirectional"))
    )
    (net (code "27") (name "GND") (class "Default")
      (node (ref "C1") (pin "1") (pinfunction "1_1") (pintype "passive"))
      (node (ref "C10") (pin "-") (pinfunction "-_-") (pintype "passive"))
      (node (ref "C11") (pin "-") (pinfunction "-_-") (pintype "passive"))
      (node (ref "C12") (pin "2") (pinfunction "2_2") (pintype "passive"))
      (node (ref "C13") (pin "2") (pinfunction "2_2") (pintype "passive"))
      (node (ref "C14") (pin "2") (pinfunction "2_2") (pintype "passive"))
      (node (ref "C2") (pin "1") (pinfunction "1_1") (pintype "passive"))
      (node (ref "C3") (pin "1") (pinfunction "1_1") (pintype "passive"))
      (node (ref "C4") (pin "1") (pinfunction "1_1") (pintype "passive"))
      (node (ref "C5") (pin "1") (pinfunction "1_1") (pintype "passive"))
      (node (ref "C7") (pin "1") (pinfunction "1_1") (pintype "passive"))
      (node (ref "C8") (pin "2") (pinfunction "2_2") (pintype "passive"))
      (node (ref "ICSP") (pin "6") (pinfunction "6_6") (pintype "bidirectional"))
      (node (ref "JP1") (pin "5") (pinfunction "CTS_5") (pintype "passive"))
      (node (ref "JP1") (pin "6") (pinfunction "GND_6") (pintype "passive"))
      (node (ref "JP2") (pin "3") (pinfunction "3_3") (pintype "passive"))
      (node (ref "JP3") (pin "3") (pinfunction "3_3") (pintype "passive"))
      (node (ref "Q1") (pin "2") (pinfunction "E_2") (pintype "passive"))
      (node (ref "Q2") (pin "2") (pinfunction "E_2") (pintype "passive"))
      (node (ref "R1") (pin "1") (pinfunction "1_1") (pintype "passive"))
      (node (ref "R10") (pin "1") (pinfunction "1_1") (pintype "passive"))
      (node (ref "R11") (pin "1") (pinfunction "1_1") (pintype "passive"))
      (node (ref "R12") (pin "1") (pinfunction "1_1") (pintype "passive"))
      (node (ref "R13") (pin "1") (pinfunction "1_1") (pintype "passive"))
      (node (ref "R14") (pin "1") (pinfunction "1_1") (pintype "passive"))
      (node (ref "R15") (pin "1") (pinfunction "1_1") (pintype "passive"))
      (node (ref "R16") (pin "1") (pinfunction "1_1") (pintype "passive"))
      (node (ref "R17") (pin "1") (pinfunction "1_1") (pintype "passive"))
      (node (ref "R18") (pin "1") (pinfunction "1_1") (pintype "passive"))
      (node (ref "R19") (pin "1") (pinfunction "1_1") (pintype "passive"))
      (node (ref "R20") (pin "1") (pinfunction "1_1") (pintype "passive"))
      (node (ref "R21") (pin "1") (pinfunction "1_1") (pintype "passive"))
      (node (ref "R22") (pin "1") (pinfunction "1_1") (pintype "passive"))
      (node (ref "R23") (pin "1") (pinfunction "1_1") (pintype "passive"))
      (node (ref "R24") (pin "1") (pinfunction "1_1") (pintype "passive"))
      (node (ref "R25") (pin "1") (pinfunction "1_1") (pintype "passive"))
      (node (ref "R26") (pin "1") (pinfunction "1_1") (pintype "passive"))
      (node (ref "R27") (pin "1") (pinfunction "1_1") (pintype "passive"))
      (node (ref "R28") (pin "1") (pinfunction "1_1") (pintype "passive"))
      (node (ref "R29") (pin "1") (pinfunction "1_1") (pintype "passive"))
      (node (ref "R30") (pin "1") (pinfunction "1_1") (pintype "passive"))
      (node (ref "R31") (pin "1") (pinfunction "1_1") (pintype "passive"))
      (node (ref "R32") (pin "1") (pinfunction "1_1") (pintype "passive"))
      (node (ref "R43") (pin "1") (pinfunction "1_1") (pintype "passive"))
      (node (ref "R8") (pin "2") (pinfunction "2_2") (pintype "passive"))
      (node (ref "R9") (pin "1") (pinfunction "1_1") (pintype "passive"))
      (node (ref "S2") (pin "1") (pinfunction "1_1") (pintype "passive"))
      (node (ref "S2") (pin "2") (pinfunction "2_2") (pintype "passive"))
      (node (ref "U$1") (pin "12") (pinfunction "GND_12") (pintype "bidirectional"))
      (node (ref "U$2") (pin "12") (pinfunction "GND_12") (pintype "bidirectional"))
      (node (ref "U$6") (pin "12") (pinfunction "VSS_12") (pintype "bidirectional"))
      (node (ref "U1") (pin "21") (pinfunction "AGND_21") (pintype "bidirectional"))
      (node (ref "U1") (pin "3") (pinfunction "GND_3") (pintype "bidirectional"))
      (node (ref "U1") (pin "5") (pinfunction "GND_5") (pintype "bidirectional"))
    )
    (net (code "28") (name "HANDBRAKE_LIGHT") (class "Default")
      (node (ref "LED22") (pin "A") (pinfunction "A_A") (pintype "passive"))
      (node (ref "U$2") (pin "21") (pinfunction "CHAN10_21") (pintype "bidirectional"))
    )
    (net (code "29") (name "IMMOBILISER_LIGHT") (class "Default")
      (node (ref "LED18") (pin "A") (pinfunction "A_A") (pintype "passive"))
      (node (ref "U$1") (pin "19") (pinfunction "CHAN12_19") (pintype "bidirectional"))
    )
    (net (code "30") (name "LCD_RX") (class "Default")
      (node (ref "JP3") (pin "1") (pinfunction "1_1") (pintype "passive"))
      (node (ref "U1") (pin "10") (pinfunction "PD6(AIN0)_10") (pintype "bidirectional"))
    )
    (net (code "31") (name "LCD_TX") (class "Default")
      (node (ref "JP3") (pin "2") (pinfunction "2_2") (pintype "passive"))
      (node (ref "U1") (pin "11") (pinfunction "PD7(AIN1)_11") (pintype "bidirectional"))
    )
    (net (code "32") (name "LEFT_SIGNAL") (class "Default")
      (node (ref "LED5") (pin "A") (pinfunction "A_A") (pintype "passive"))
      (node (ref "U$1") (pin "16") (pinfunction "CHAN15_16") (pintype "bidirectional"))
    )
    (net (code "33") (name "LOW_FUEL_LIGHT") (class "Default")
      (node (ref "LED26") (pin "A") (pinfunction "A_A") (pintype "passive"))
      (node (ref "U$2") (pin "16") (pinfunction "CHAN15_16") (pintype "bidirectional"))
    )
    (net (code "34") (name "MAIN_BEAM_LIGHT") (class "Default")
      (node (ref "LED10") (pin "A") (pinfunction "A_A") (pintype "passive"))
      (node (ref "U$1") (pin "5") (pinfunction "CHAN4_5") (pintype "bidirectional"))
    )
    (net (code "35") (name "MUX_INPUT") (class "Default")
      (node (ref "ICSP") (pin "1") (pinfunction "1_1") (pintype "bidirectional"))
      (node (ref "U$1") (pin "1") (pinfunction "COM_1") (pintype "bidirectional"))
      (node (ref "U$2") (pin "1") (pinfunction "COM_1") (pintype "bidirectional"))
      (node (ref "U1") (pin "16") (pinfunction "PB4(MISO)_16") (pintype "bidirectional"))
    )
    (net (code "36") (name "Net-(IC1-ADJ)") (class "Default")
      (node (ref "IC1") (pin "1") (pinfunction "ADJ_1") (pintype "input"))
      (node (ref "R7") (pin "1") (pinfunction "1_1") (pintype "passive"))
      (node (ref "R8") (pin "1") (pinfunction "1_1") (pintype "passive"))
    )
    (net (code "37") (name "Net-(IC1-IN)") (class "Default")
      (node (ref "C10") (pin "+") (pinfunction "+_+") (pintype "passive"))
      (node (ref "D1") (pin "C") (pinfunction "C_C") (pintype "passive"))
      (node (ref "IC1") (pin "3") (pinfunction "IN_3") (pintype "input"))
    )
    (net (code "38") (name "Net-(LED1-PadC)") (class "Default")
      (node (ref "LED1") (pin "C") (pinfunction "C_C") (pintype "passive"))
      (node (ref "R2") (pin "2") (pinfunction "2_2") (pintype "passive"))
    )
    (net (code "39") (name "Net-(LED2-PadC)") (class "Default")
      (node (ref "LED2") (pin "C") (pinfunction "C_C") (pintype "passive"))
      (node (ref "R3") (pin "2") (pinfunction "2_2") (pintype "passive"))
    )
    (net (code "40") (name "Net-(LED3-PadC)") (class "Default")
      (node (ref "LED3") (pin "C") (pinfunction "C_C") (pintype "passive"))
      (node (ref "R4") (pin "2") (pinfunction "2_2") (pintype "passive"))
    )
    (net (code "41") (name "Net-(LED4-PadC)") (class "Default")
      (node (ref "LED4") (pin "C") (pinfunction "C_C") (pintype "passive"))
      (node (ref "R5") (pin "2") (pinfunction "2_2") (pintype "passive"))
    )
    (net (code "42") (name "Net-(LED5-PadC)") (class "Default")
      (node (ref "LED5") (pin "C") (pinfunction "C_C") (pintype "passive"))
      (node (ref "R11") (pin "2") (pinfunction "2_2") (pintype "passive"))
    )
    (net (code "43") (name "Net-(LED6-PadC)") (class "Default")
      (node (ref "LED6") (pin "C") (pinfunction "C_C") (pintype "passive"))
      (node (ref "R12") (pin "2") (pinfunction "2_2") (pintype "passive"))
    )
    (net (code "44") (name "Net-(LED7-PadC)") (class "Default")
      (node (ref "LED7") (pin "C") (pinfunction "C_C") (pintype "passive"))
      (node (ref "R13") (pin "2") (pinfunction "2_2") (pintype "passive"))
    )
    (net (code "45") (name "Net-(LED8-PadC)") (class "Default")
      (node (ref "LED8") (pin "C") (pinfunction "C_C") (pintype "passive"))
      (node (ref "R14") (pin "2") (pinfunction "2_2") (pintype "passive"))
    )
    (net (code "46") (name "Net-(LED9-PadC)") (class "Default")
      (node (ref "LED9") (pin "C") (pinfunction "C_C") (pintype "passive"))
      (node (ref "R15") (pin "2") (pinfunction "2_2") (pintype "passive"))
    )
    (net (code "47") (name "Net-(LED10-PadC)") (class "Default")
      (node (ref "LED10") (pin "C") (pinfunction "C_C") (pintype "passive"))
      (node (ref "R16") (pin "2") (pinfunction "2_2") (pintype "passive"))
    )
    (net (code "48") (name "Net-(LED11-PadC)") (class "Default")
      (node (ref "LED11") (pin "C") (pinfunction "C_C") (pintype "passive"))
      (node (ref "R17") (pin "2") (pinfunction "2_2") (pintype "passive"))
    )
    (net (code "49") (name "Net-(LED12-PadC)") (class "Default")
      (node (ref "LED12") (pin "C") (pinfunction "C_C") (pintype "passive"))
      (node (ref "R18") (pin "2") (pinfunction "2_2") (pintype "passive"))
    )
    (net (code "50") (name "Net-(LED13-PadC)") (class "Default")
      (node (ref "LED13") (pin "C") (pinfunction "C_C") (pintype "passive"))
      (node (ref "R19") (pin "2") (pinfunction "2_2") (pintype "passive"))
    )
    (net (code "51") (name "Net-(LED14-PadC)") (class "Default")
      (node (ref "LED14") (pin "C") (pinfunction "C_C") (pintype "passive"))
      (node (ref "R20") (pin "2") (pinfunction "2_2") (pintype "passive"))
    )
    (net (code "52") (name "Net-(LED15-PadC)") (class "Default")
      (node (ref "LED15") (pin "C") (pinfunction "C_C") (pintype "passive"))
      (node (ref "R21") (pin "2") (pinfunction "2_2") (pintype "passive"))
    )
    (net (code "53") (name "Net-(LED16-PadC)") (class "Default")
      (node (ref "LED16") (pin "C") (pinfunction "C_C") (pintype "passive"))
      (node (ref "R22") (pin "2") (pinfunction "2_2") (pintype "passive"))
    )
    (net (code "54") (name "Net-(LED17-PadC)") (class "Default")
      (node (ref "LED17") (pin "C") (pinfunction "C_C") (pintype "passive"))
      (node (ref "R23") (pin "2") (pinfunction "2_2") (pintype "passive"))
    )
    (net (code "55") (name "Net-(LED18-PadC)") (class "Default")
      (node (ref "LED18") (pin "C") (pinfunction "C_C") (pintype "passive"))
      (node (ref "R24") (pin "2") (pinfunction "2_2") (pintype "passive"))
    )
    (net (code "56") (name "Net-(LED19-PadC)") (class "Default")
      (node (ref "LED19") (pin "C") (pinfunction "C_C") (pintype "passive"))
      (node (ref "R25") (pin "2") (pinfunction "2_2") (pintype "passive"))
    )
    (net (code "57") (name "Net-(LED20-PadC)") (class "Default")
      (node (ref "LED20") (pin "C") (pinfunction "C_C") (pintype "passive"))
      (node (ref "R26") (pin "2") (pinfunction "2_2") (pintype "passive"))
    )
    (net (code "58") (name "Net-(LED21-PadC)") (class "Default")
      (node (ref "LED21") (pin "C") (pinfunction "C_C") (pintype "passive"))
      (node (ref "R27") (pin "2") (pinfunction "2_2") (pintype "passive"))
    )
    (net (code "59") (name "Net-(LED22-PadC)") (class "Default")
      (node (ref "LED22") (pin "C") (pinfunction "C_C") (pintype "passive"))
      (node (ref "R28") (pin "2") (pinfunction "2_2") (pintype "passive"))
    )
    (net (code "60") (name "Net-(LED23-PadC)") (class "Default")
      (node (ref "LED23") (pin "C") (pinfunction "C_C") (pintype "passive"))
      (node (ref "R29") (pin "2") (pinfunction "2_2") (pintype "passive"))
    )
    (net (code "61") (name "Net-(LED24-PadC)") (class "Default")
      (node (ref "LED24") (pin "C") (pinfunction "C_C") (pintype "passive"))
      (node (ref "R30") (pin "2") (pinfunction "2_2") (pintype "passive"))
    )
    (net (code "62") (name "Net-(LED25-PadC)") (class "Default")
      (node (ref "LED25") (pin "C") (pinfunction "C_C") (pintype "passive"))
      (node (ref "R31") (pin "2") (pinfunction "2_2") (pintype "passive"))
    )
    (net (code "63") (name "Net-(LED26-PadC)") (class "Default")
      (node (ref "LED26") (pin "C") (pinfunction "C_C") (pintype "passive"))
      (node (ref "R32") (pin "2") (pinfunction "2_2") (pintype "passive"))
    )
    (net (code "64") (name "Net-(LED27-PadC)") (class "Default")
      (node (ref "LED27") (pin "C") (pinfunction "C_C") (pintype "passive"))
      (node (ref "R33") (pin "2") (pinfunction "2_2") (pintype "passive"))
    )
    (net (code "65") (name "Net-(LED28-PadC)") (class "Default")
      (node (ref "LED28") (pin "C") (pinfunction "C_C") (pintype "passive"))
      (node (ref "R34") (pin "2") (pinfunction "2_2") (pintype "passive"))
    )
    (net (code "66") (name "Net-(LED29-PadC)") (class "Default")
      (node (ref "LED29") (pin "C") (pinfunction "C_C") (pintype "passive"))
      (node (ref "R35") (pin "2") (pinfunction "2_2") (pintype "passive"))
    )
    (net (code "67") (name "Net-(LED30-PadC)") (class "Default")
      (node (ref "LED30") (pin "C") (pinfunction "C_C") (pintype "passive"))
      (node (ref "R36") (pin "2") (pinfunction "2_2") (pintype "passive"))
    )
    (net (code "68") (name "Net-(LED31-PadC)") (class "Default")
      (node (ref "LED31") (pin "C") (pinfunction "C_C") (pintype "passive"))
      (node (ref "R37") (pin "2") (pinfunction "2_2") (pintype "passive"))
    )
    (net (code "69") (name "Net-(LED32-PadC)") (class "Default")
      (node (ref "LED32") (pin "C") (pinfunction "C_C") (pintype "passive"))
      (node (ref "R38") (pin "2") (pinfunction "2_2") (pintype "passive"))
    )
    (net (code "70") (name "Net-(LED33-PadC)") (class "Default")
      (node (ref "LED33") (pin "C") (pinfunction "C_C") (pintype "passive"))
      (node (ref "R39") (pin "2") (pinfunction "2_2") (pintype "passive"))
    )
    (net (code "71") (name "Net-(LED34-PadC)") (class "Default")
      (node (ref "LED34") (pin "C") (pinfunction "C_C") (pintype "passive"))
      (node (ref "R40") (pin "2") (pinfunction "2_2") (pintype "passive"))
    )
    (net (code "72") (name "Net-(LED35-PadC)") (class "Default")
      (node (ref "LED35") (pin "C") (pinfunction "C_C") (pintype "passive"))
      (node (ref "R41") (pin "2") (pinfunction "2_2") (pintype "passive"))
    )
    (net (code "73") (name "Net-(LED36-PadC)") (class "Default")
      (node (ref "LED36") (pin "C") (pinfunction "C_C") (pintype "passive"))
      (node (ref "R42") (pin "2") (pinfunction "2_2") (pintype "passive"))
    )
    (net (code "74") (name "Net-(LED37-PadC)") (class "Default")
      (node (ref "LED37") (pin "C") (pinfunction "C_C") (pintype "passive"))
      (node (ref "R43") (pin "2") (pinfunction "2_2") (pintype "passive"))
    )
    (net (code "75") (name "Net-(Q1-C)") (class "Default")
      (node (ref "Q1") (pin "3") (pinfunction "C_3") (pintype "passive"))
      (node (ref "R2") (pin "1") (pinfunction "1_1") (pintype "passive"))
      (node (ref "R3") (pin "1") (pinfunction "1_1") (pintype "passive"))
      (node (ref "R33") (pin "1") (pinfunction "1_1") (pintype "passive"))
      (node (ref "R34") (pin "1") (pinfunction "1_1") (pintype "passive"))
      (node (ref "R35") (pin "1") (pinfunction "1_1") (pintype "passive"))
      (node (ref "R36") (pin "1") (pinfunction "1_1") (pintype "passive"))
      (node (ref "R37") (pin "1") (pinfunction "1_1") (pintype "passive"))
      (node (ref "R38") (pin "1") (pinfunction "1_1") (pintype "passive"))
      (node (ref "R39") (pin "1") (pinfunction "1_1") (pintype "passive"))
      (node (ref "R4") (pin "1") (pinfunction "1_1") (pintype "passive"))
      (node (ref "R40") (pin "1") (pinfunction "1_1") (pintype "passive"))
      (node (ref "R41") (pin "1") (pinfunction "1_1") (pintype "passive"))
      (node (ref "R42") (pin "1") (pinfunction "1_1") (pintype "passive"))
      (node (ref "R5") (pin "1") (pinfunction "1_1") (pintype "passive"))
    )
    (net (code "76") (name "Net-(Q2-C)") (class "Default")
      (node (ref "Q2") (pin "3") (pinfunction "C_3") (pintype "passive"))
      (node (ref "SG1") (pin "-") (pinfunction "2_-") (pintype "passive"))
    )
    (net (code "77") (name "Net-(U1-AREF)") (class "Default")
      (node (ref "C7") (pin "2") (pinfunction "2_2") (pintype "passive"))
      (node (ref "U1") (pin "20") (pinfunction "AREF_20") (pintype "bidirectional"))
    )
    (net (code "78") (name "Net-(U1-PB6(XTAL1{slash}TOSC1))") (class "Default")
      (node (ref "C4") (pin "2") (pinfunction "2_2") (pintype "passive"))
      (node (ref "U1") (pin "7") (pinfunction "PB6(XTAL1/TOSC1)_7") (pintype "bidirectional"))
      (node (ref "Y1") (pin "2") (pinfunction "2_2") (pintype "passive"))
    )
    (net (code "79") (name "Net-(U1-PB7(XTAL2{slash}TOSC2))") (class "Default")
      (node (ref "C5") (pin "2") (pinfunction "2_2") (pintype "passive"))
      (node (ref "U1") (pin "8") (pinfunction "PB7(XTAL2/TOSC2)_8") (pintype "bidirectional"))
      (node (ref "Y1") (pin "1") (pinfunction "1_1") (pintype "passive"))
    )
    (net (code "80") (name "OIL_WARNING_LIGHT") (class "Default")
      (node (ref "LED20") (pin "A") (pinfunction "A_A") (pintype "passive"))
      (node (ref "U$2") (pin "23") (pinfunction "CHAN8_23") (pintype "bidirectional"))
    )
    (net (code "81") (name "OUT1A") (class "Default")
      (node (ref "M1") (pin "P$1") (pinfunction "P$1_P$1") (pintype "bidirectional"))
      (node (ref "U$6") (pin "7") (pinfunction "OUT1A_7") (pintype "bidirectional"))
    )
    (net (code "82") (name "OUT1B") (class "Default")
      (node (ref "M2") (pin "P$1") (pinfunction "P$1_P$1") (pintype "bidirectional"))
      (node (ref "U$6") (pin "22") (pinfunction "OUT1B_22") (pintype "bidirectional"))
    )
    (net (code "83") (name "OUT1C") (class "Default")
      (node (ref "M3") (pin "P$1") (pinfunction "P$1_P$1") (pintype "bidirectional"))
      (node (ref "U$6") (pin "21") (pinfunction "OUT1C_21") (pintype "bidirectional"))
    )
    (net (code "84") (name "OUT1D") (class "Default")
      (node (ref "M4") (pin "P$1") (pinfunction "P$1_P$1") (pintype "bidirectional"))
      (node (ref "U$6") (pin "8") (pinfunction "OUT1D_8") (pintype "bidirectional"))
    )
    (net (code "85") (name "OUT2A") (class "Default")
      (node (ref "M1") (pin "P$2") (pinfunction "P$2_P$2") (pintype "bidirectional"))
      (node (ref "U$6") (pin "6") (pinfunction "OUT2A_6") (pintype "bidirectional"))
    )
    (net (code "86") (name "OUT2B") (class "Default")
      (node (ref "M2") (pin "P$2") (pinfunction "P$2_P$2") (pintype "bidirectional"))
      (node (ref "U$6") (pin "23") (pinfunction "OUT2B_23") (pintype "bidirectional"))
    )
    (net (code "87") (name "OUT2C") (class "Default")
      (node (ref "M3") (pin "P$2") (pinfunction "P$2_P$2") (pintype "bidirectional"))
      (node (ref "U$6") (pin "20") (pinfunction "OUT2C_20") (pintype "bidirectional"))
    )
    (net (code "88") (name "OUT2D") (class "Default")
      (node (ref "M4") (pin "P$2") (pinfunction "P$2_P$2") (pintype "bidirectional"))
      (node (ref "U$6") (pin "9") (pinfunction "OUT2D_9") (pintype "bidirectional"))
    )
    (net (code "89") (name "OUT3A") (class "Default")
      (node (ref "M1") (pin "P$3") (pinfunction "P$3_P$3") (pintype "bidirectional"))
      (node (ref "U$6") (pin "4") (pinfunction "OUT3A_4") (pintype "bidirectional"))
    )
    (net (code "90") (name "OUT3B") (class "Default")
      (node (ref "M2") (pin "P$3") (pinfunction "P$3_P$3") (pintype "bidirectional"))
      (node (ref "U$6") (pin "25") (pinfunction "OUT3B_25") (pintype "bidirectional"))
    )
    (net (code "91") (name "OUT3C") (class "Default")
      (node (ref "M3") (pin "P$3") (pinfunction "P$3_P$3") (pintype "bidirectional"))
      (node (ref "U$6") (pin "18") (pinfunction "OUT3C_18") (pintype "bidirectional"))
    )
    (net (code "92") (name "OUT3D") (class "Default")
      (node (ref "M4") (pin "P$3") (pinfunction "P$3_P$3") (pintype "bidirectional"))
      (node (ref "U$6") (pin "11") (pinfunction "OUT3D_11") (pintype "bidirectional"))
    )
    (net (code "93") (name "OUT4A") (class "Default")
      (node (ref "M1") (pin "P$4") (pinfunction "P$4_P$4") (pintype "bidirectional"))
      (node (ref "U$6") (pin "5") (pinfunction "OUT4A_5") (pintype "bidirectional"))
    )
    (net (code "94") (name "OUT4B") (class "Default")
      (node (ref "M2") (pin "P$4") (pinfunction "P$4_P$4") (pintype "bidirectional"))
      (node (ref "U$6") (pin "24") (pinfunction "OUT4B_24") (pintype "bidirectional"))
    )
    (net (code "95") (name "OUT4C") (class "Default")
      (node (ref "M3") (pin "P$4") (pinfunction "P$4_P$4") (pintype "bidirectional"))
      (node (ref "U$6") (pin "19") (pinfunction "OUT4C_19") (pintype "bidirectional"))
    )
    (net (code "96") (name "OUT4D") (class "Default")
      (node (ref "M4") (pin "P$4") (pinfunction "P$4_P$4") (pintype "bidirectional"))
      (node (ref "U$6") (pin "10") (pinfunction "OUT4D_10") (pintype "bidirectional"))
    )
    (net (code "97") (name "PANEL_BACKLIGHT") (class "Default")
      (node (ref "Q1") (pin "1") (pinfunction "B_1") (pintype "passive"))
      (node (ref "U$1") (pin "17") (pinfunction "CHAN14_17") (pintype "bidirectional"))
    )
    (net (code "98") (name "REAR_DOORS_OPEN") (class "Default")
      (node (ref "LED17") (pin "A") (pinfunction "A_A") (pintype "passive"))
      (node (ref "U$1") (pin "21") (pinfunction "CHAN10_21") (pintype "bidirectional"))
    )
    (net (code "99") (name "REAR_FOG_LIGHT") (class "Default")
      (node (ref "LED12") (pin "A") (pinfunction "A_A") (pintype "passive"))
      (node (ref "U$1") (pin "3") (pinfunction "CHAN6_3") (pintype "bidirectional"))
    )
    (net (code "100") (name "RESET") (class "Default")
      (node (ref "C6") (pin "2") (pinfunction "2_2") (pintype "passive"))
      (node (ref "ICSP") (pin "5") (pinfunction "5_5") (pintype "bidirectional"))
      (node (ref "R6") (pin "1") (pinfunction "1_1") (pintype "passive"))
      (node (ref "S2") (pin "3") (pinfunction "3_3") (pintype "passive"))
      (node (ref "S2") (pin "4") (pinfunction "4_4") (pintype "passive"))
      (node (ref "U1") (pin "29") (pinfunction "PC6(/RESET)_29") (pintype "bidirectional"))
    )
    (net (code "101") (name "RIGHT_SIGNAL") (class "Default")
      (node (ref "LED19") (pin "A") (pinfunction "A_A") (pintype "passive"))
      (node (ref "U$2") (pin "3") (pinfunction "CHAN6_3") (pintype "bidirectional"))
    )
    (net (code "102") (name "RXD") (class "Default")
      (node (ref "JP1") (pin "3") (pinfunction "TXO_3") (pintype "passive"))
      (node (ref "JP2") (pin "1") (pinfunction "1_1") (pintype "passive"))
      (node (ref "U1") (pin "30") (pinfunction "PD0(RXD)_30") (pintype "bidirectional"))
    )
    (net (code "103") (name "S0") (class "Default")
      (node (ref "U$1") (pin "10") (pinfunction "S0_10") (pintype "input"))
      (node (ref "U$2") (pin "10") (pinfunction "S0_10") (pintype "input"))
      (node (ref "U1") (pin "12") (pinfunction "PB0(ICP)_12") (pintype "bidirectional"))
    )
    (net (code "104") (name "S1") (class "Default")
      (node (ref "U$1") (pin "11") (pinfunction "S1_11") (pintype "input"))
      (node (ref "U$2") (pin "11") (pinfunction "S1_11") (pintype "input"))
      (node (ref "U1") (pin "13") (pinfunction "PB1(OC1A)_13") (pintype "bidirectional"))
    )
    (net (code "105") (name "S2") (class "Default")
      (node (ref "U$1") (pin "14") (pinfunction "S2_14") (pintype "input"))
      (node (ref "U$2") (pin "14") (pinfunction "S2_14") (pintype "input"))
      (node (ref "U1") (pin "14") (pinfunction "PB2(SS/OC1B)_14") (pintype "bidirectional"))
    )
    (net (code "106") (name "S3") (class "Default")
      (node (ref "ICSP") (pin "4") (pinfunction "4_4") (pintype "bidirectional"))
      (node (ref "U$1") (pin "13") (pinfunction "S3_13") (pintype "input"))
      (node (ref "U$2") (pin "13") (pinfunction "S3_13") (pintype "input"))
      (node (ref "U1") (pin "15") (pinfunction "PB3(MOSI/OC2)_15") (pintype "bidirectional"))
    )
    (net (code "107") (name "SERVICE_WARNING") (class "Default")
      (node (ref "LED14") (pin "A") (pinfunction "A_A") (pintype "passive"))
      (node (ref "U$1") (pin "18") (pinfunction "CHAN13_18") (pintype "bidirectional"))
    )
    (net (code "108") (name "STOP_WARNING") (class "Default")
      (node (ref "LED15") (pin "A") (pinfunction "A_A") (pintype "passive"))
      (node (ref "U$1") (pin "20") (pinfunction "CHAN11_20") (pintype "bidirectional"))
    )
    (net (code "109") (name "TXD") (class "Default")
      (node (ref "JP1") (pin "2") (pinfunction "RXI_2") (pintype "passive"))
      (node (ref "JP2") (pin "2") (pinfunction "2_2") (pintype "passive"))
      (node (ref "U1") (pin "31") (pinfunction "PD1(TXD)_31") (pintype "bidirectional"))
    )
    (net (code "110") (name "unconnected-(U$1-CHAN8-Pad23)") (class "Default")
      (node (ref "U$1") (pin "23") (pinfunction "CHAN8_23") (pintype "bidirectional"))
    )
    (net (code "111") (name "unconnected-(U$2-CHAN0-Pad9)") (class "Default")
      (node (ref "U$2") (pin "9") (pinfunction "CHAN0_9") (pintype "bidirectional"))
    )
    (net (code "112") (name "unconnected-(U$2-CHAN1-Pad8)") (class "Default")
      (node (ref "U$2") (pin "8") (pinfunction "CHAN1_8") (pintype "bidirectional"))
    )
    (net (code "113") (name "unconnected-(U$2-CHAN2-Pad7)") (class "Default")
      (node (ref "U$2") (pin "7") (pinfunction "CHAN2_7") (pintype "bidirectional"))
    )
    (net (code "114") (name "unconnected-(U$2-CHAN3-Pad6)") (class "Default")
      (node (ref "U$2") (pin "6") (pinfunction "CHAN3_6") (pintype "bidirectional"))
    )
    (net (code "115") (name "unconnected-(U$2-CHAN4-Pad5)") (class "Default")
      (node (ref "U$2") (pin "5") (pinfunction "CHAN4_5") (pintype "bidirectional"))
    )
    (net (code "116") (name "unconnected-(U$2-CHAN5-Pad4)") (class "Default")
      (node (ref "U$2") (pin "4") (pinfunction "CHAN5_4") (pintype "bidirectional"))
    )
    (net (code "117") (name "unconnected-(U1-ADC6-Pad19)") (class "Default")
      (node (ref "U1") (pin "19") (pinfunction "ADC6_19") (pintype "bidirectional"))
    )
    (net (code "118") (name "unconnected-(U1-ADC7-Pad22)") (class "Default")
      (node (ref "U1") (pin "22") (pinfunction "ADC7_22") (pintype "bidirectional"))
    )
    (net (code "119") (name "~{RESET}") (class "Default")
      (node (ref "ICSP") (pin "3") (pinfunction "3_3") (pintype "bidirectional"))
      (node (ref "R1") (pin "2") (pinfunction "2_2") (pintype "passive"))
      (node (ref "U$6") (pin "26") (pinfunction "~{RESET}_26") (pintype "bidirectional"))
      (node (ref "U1") (pin "17") (pinfunction "PB5(SCK)_17") (pintype "bidirectional"))
    )
  )
)
